# attiny85.net
KiCad netlist of a schematic drawn in EAGLE
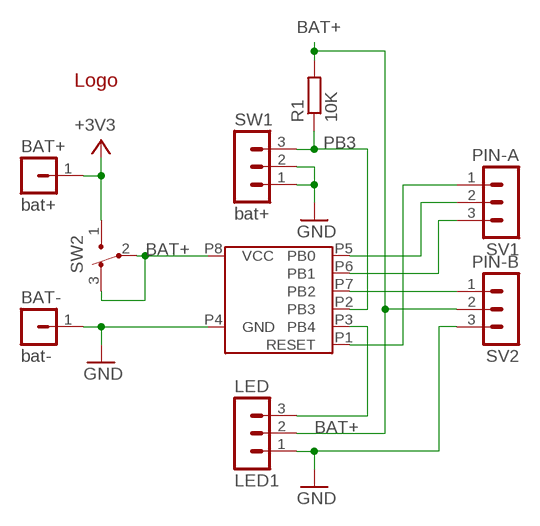
[diagram p0: schematic, sheet 1]

(export (version "E")
  (design (tool "Eeschema 10.0.6"))
  (components
    (comp (ref "ATTINY85-1")
      (value "ATTINY85")
      (footprint "eagle-import:ATTINY85-20SUR")
      (libsource (lib "eagle-import") (part "ATTINY85SOP8"))
    )
    (comp (ref "BAT+")
      (value "bat+")
      (footprint "eagle-import:PINHEAD-MA01-1")
      (libsource (lib "eagle-import") (part "PINHEAD-MA01-1"))
    )
    (comp (ref "BAT-")
      (value "bat-")
      (footprint "eagle-import:PINHEAD-MA01-1")
      (libsource (lib "eagle-import") (part "PINHEAD-MA01-1"))
    )
    (comp (ref "LED")
      (value "LED1")
      (footprint "eagle-import:PINHEAD-MA03-1")
      (libsource (lib "eagle-import") (part "ytani1_30941153_PINHEAD-MA03-1"))
    )
    (comp (ref "LOGO4")
      (value "LOGO-YTLOGO2-BOTTOM")
      (footprint "eagle-import:LOGO-YT2-BOTTOM")
      (libsource (lib "eagle-import") (part "LOGO-YTLOGO2-BOTTOM"))
    )
    (comp (ref "R1")
      (value "10K")
      (footprint "eagle-import:M3216")
      (libsource (lib "eagle-import") (part "R-EU_M3216"))
    )
    (comp (ref "SV1")
      (value "PIN-A")
      (footprint "eagle-import:PINHEAD-MA03-1")
      (libsource (lib "eagle-import") (part "PINHEAD-MA03-1"))
    )
    (comp (ref "SV2")
      (value "PIN-B")
      (footprint "eagle-import:PINHEAD-MA03-1")
      (libsource (lib "eagle-import") (part "PINHEAD-MA03-1"))
    )
    (comp (ref "SW1")
      (value "bat+")
      (footprint "eagle-import:PINHEAD-MA03-1")
      (libsource (lib "eagle-import") (part "PINHEAD-MA03-1"))
    )
    (comp (ref "SW2")
      (value "POWER")
      (footprint "eagle-import:SW3-1")
      (fields (field (name "MF") "HiLetgo"))
      (libsource (lib "eagle-import") (part "SW3-1"))
    )
  )
  (nets
    (net (code "1") (name "+3V3") (class "Default")
      (node (ref "BAT+") (pin "1") (pinfunction "1_1") (pintype "passive"))
      (node (ref "SW2") (pin "1") (pinfunction "1_1") (pintype "passive"))
    )
    (net (code "2") (name "/BAT+") (class "Default")
      (node (ref "ATTINY85-1") (pin "P8") (pinfunction "VCC_P8") (pintype "bidirectional"))
      (node (ref "LED") (pin "2") (pinfunction "2_2") (pintype "passive"))
      (node (ref "R1") (pin "2") (pinfunction "2_2") (pintype "passive"))
      (node (ref "SV2") (pin "2") (pinfunction "2_2") (pintype "passive"))
      (node (ref "SW2") (pin "2") (pinfunction "2_2") (pintype "passive"))
      (node (ref "SW2") (pin "3") (pinfunction "3_3") (pintype "passive"))
    )
    (net (code "3") (name "/PB3") (class "Default")
      (node (ref "ATTINY85-1") (pin "P2") (pinfunction "PB3_P2") (pintype "bidirectional"))
      (node (ref "R1") (pin "1") (pinfunction "1_1") (pintype "passive"))
      (node (ref "SW1") (pin "3") (pinfunction "3_3") (pintype "passive"))
    )
    (net (code "4") (name "GND") (class "Default")
      (node (ref "ATTINY85-1") (pin "P4") (pinfunction "GND_P4") (pintype "bidirectional"))
      (node (ref "BAT-") (pin "1") (pinfunction "1_1") (pintype "passive"))
      (node (ref "LED") (pin "1") (pinfunction "1_1") (pintype "passive"))
      (node (ref "SV2") (pin "3") (pinfunction "3_3") (pintype "passive"))
      (node (ref "SW1") (pin "1") (pinfunction "1_1") (pintype "passive"))
      (node (ref "SW1") (pin "2") (pinfunction "2_2") (pintype "passive"))
    )
    (net (code "5") (name "Net-(ATTINY85-1-PB0)") (class "Default")
      (node (ref "ATTINY85-1") (pin "P5") (pinfunction "PB0_P5") (pintype "bidirectional"))
      (node (ref "SV1") (pin "2") (pinfunction "2_2") (pintype "passive"))
    )
    (net (code "6") (name "Net-(ATTINY85-1-PB1)") (class "Default")
      (node (ref "ATTINY85-1") (pin "P6") (pinfunction "PB1_P6") (pintype "bidirectional"))
      (node (ref "SV1") (pin "3") (pinfunction "3_3") (pintype "passive"))
    )
    (net (code "7") (name "Net-(ATTINY85-1-PB2)") (class "Default")
      (node (ref "ATTINY85-1") (pin "P7") (pinfunction "PB2_P7") (pintype "bidirectional"))
      (node (ref "SV2") (pin "1") (pinfunction "1_1") (pintype "passive"))
    )
    (net (code "8") (name "Net-(ATTINY85-1-PB4)") (class "Default")
      (node (ref "ATTINY85-1") (pin "P3") (pinfunction "PB4_P3") (pintype "bidirectional"))
      (node (ref "LED") (pin "3") (pinfunction "3_3") (pintype "passive"))
    )
    (net (code "9") (name "Net-(ATTINY85-1-RESET)") (class "Default")
      (node (ref "ATTINY85-1") (pin "P1") (pinfunction "RESET_P1") (pintype "bidirectional"))
      (node (ref "SV1") (pin "1") (pinfunction "1_1") (pintype "passive"))
    )
  )
)
